# Segment_Register.net
KiCad netlist of a schematic drawn in Altium Designer
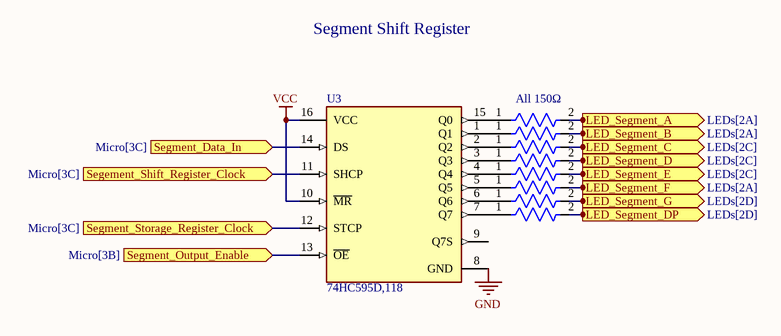
[diagram p0: Segment_Register.SchDoc]

(export (version "E")
  (design (tool "Eeschema 10.0.6"))
  (components
    (comp (ref "R2")
      (value "CRCW0402150RFKED")
      (footprint "FP-CRCW0402-e3-IPC_A")
      (description "RES Thick Film, 150Ω, 1%, 0.063W, 100ppm/°C, 0402")
      (fields (field (name "TOLERANCE") "1%"))
      (libsource (lib "Altium Content Vault") (part "1029c3af85768c4190bb7ad29bc67b5"))
    )
    (comp (ref "R3")
      (value "CRCW0402150RFKED")
      (footprint "FP-CRCW0402-e3-IPC_A")
      (description "RES Thick Film, 150Ω, 1%, 0.063W, 100ppm/°C, 0402")
      (fields (field (name "TOLERANCE") "1%"))
      (libsource (lib "Altium Content Vault") (part "1029c3af85768c4190bb7ad29bc67b5"))
    )
    (comp (ref "R4")
      (value "CRCW0402150RFKED")
      (footprint "FP-CRCW0402-e3-IPC_A")
      (description "RES Thick Film, 150Ω, 1%, 0.063W, 100ppm/°C, 0402")
      (fields (field (name "TOLERANCE") "1%"))
      (libsource (lib "Altium Content Vault") (part "1029c3af85768c4190bb7ad29bc67b5"))
    )
    (comp (ref "R5")
      (value "CRCW0402150RFKED")
      (footprint "FP-CRCW0402-e3-IPC_A")
      (description "RES Thick Film, 150Ω, 1%, 0.063W, 100ppm/°C, 0402")
      (fields (field (name "TOLERANCE") "1%"))
      (libsource (lib "Altium Content Vault") (part "1029c3af85768c4190bb7ad29bc67b5"))
    )
    (comp (ref "R6")
      (value "CRCW0402150RFKED")
      (footprint "FP-CRCW0402-e3-IPC_A")
      (description "RES Thick Film, 150Ω, 1%, 0.063W, 100ppm/°C, 0402")
      (fields (field (name "TOLERANCE") "1%"))
      (libsource (lib "Altium Content Vault") (part "1029c3af85768c4190bb7ad29bc67b5"))
    )
    (comp (ref "R7")
      (value "CRCW0402150RFKED")
      (footprint "FP-CRCW0402-e3-IPC_A")
      (description "RES Thick Film, 150Ω, 1%, 0.063W, 100ppm/°C, 0402")
      (fields (field (name "TOLERANCE") "1%"))
      (libsource (lib "Altium Content Vault") (part "1029c3af85768c4190bb7ad29bc67b5"))
    )
    (comp (ref "R8")
      (value "CRCW0402150RFKED")
      (footprint "FP-CRCW0402-e3-IPC_A")
      (description "RES Thick Film, 150Ω, 1%, 0.063W, 100ppm/°C, 0402")
      (fields (field (name "TOLERANCE") "1%"))
      (libsource (lib "Altium Content Vault") (part "1029c3af85768c4190bb7ad29bc67b5"))
    )
    (comp (ref "R9")
      (value "CRCW0402150RFKED")
      (footprint "FP-CRCW0402-e3-IPC_A")
      (description "RES Thick Film, 150Ω, 1%, 0.063W, 100ppm/°C, 0402")
      (fields (field (name "TOLERANCE") "1%"))
      (libsource (lib "Altium Content Vault") (part "1029c3af85768c4190bb7ad29bc67b5"))
    )
    (comp (ref "U3")
      (value "74HC595D,118")
      (footprint "FP-SOT109-1-IPC_C")
      (description "IC SHIFT REGISTER 8BIT 16SOIC")
      (libsource (lib "Altium Content Vault") (part "7b153f231cfcc3ac06dee253bd56617"))
    )
  )
  (nets
    (net (code "1") (name "/LED_Segment_A") (class "Default")
      (node (ref "R2") (pin "2") (pinfunction "2_2") (pintype "passive"))
    )
    (net (code "2") (name "/LED_Segment_B") (class "Default")
      (node (ref "R3") (pin "2") (pinfunction "2_2") (pintype "passive"))
    )
    (net (code "3") (name "/LED_Segment_C") (class "Default")
      (node (ref "R4") (pin "2") (pinfunction "2_2") (pintype "passive"))
    )
    (net (code "4") (name "/LED_Segment_D") (class "Default")
      (node (ref "R5") (pin "2") (pinfunction "2_2") (pintype "passive"))
    )
    (net (code "5") (name "/LED_Segment_DP") (class "Default")
      (node (ref "R9") (pin "2") (pinfunction "2_2") (pintype "passive"))
    )
    (net (code "6") (name "/LED_Segment_E") (class "Default")
      (node (ref "R6") (pin "2") (pinfunction "2_2") (pintype "passive"))
    )
    (net (code "7") (name "/LED_Segment_F") (class "Default")
      (node (ref "R7") (pin "2") (pinfunction "2_2") (pintype "passive"))
    )
    (net (code "8") (name "/LED_Segment_G") (class "Default")
      (node (ref "R8") (pin "2") (pinfunction "2_2") (pintype "passive"))
    )
    (net (code "9") (name "/Segement_Shift_Register_Clock") (class "Default")
      (node (ref "U3") (pin "11") (pinfunction "SHCP_11") (pintype "input"))
    )
    (net (code "10") (name "/Segment_Data_In") (class "Default")
      (node (ref "U3") (pin "14") (pinfunction "DS_14") (pintype "input"))
    )
    (net (code "11") (name "/Segment_Output_Enable") (class "Default")
      (node (ref "U3") (pin "13") (pinfunction "~{OE}_13") (pintype "input"))
    )
    (net (code "12") (name "/Segment_Storage_Register_Clock") (class "Default")
      (node (ref "U3") (pin "12") (pinfunction "STCP_12") (pintype "input"))
    )
    (net (code "13") (name "GND") (class "Default")
      (node (ref "U3") (pin "8") (pinfunction "GND_8") (pintype "power_in"))
    )
    (net (code "14") (name "Net-(U3-Q0)") (class "Default")
      (node (ref "R2") (pin "1") (pinfunction "1_1") (pintype "passive"))
      (node (ref "U3") (pin "15") (pinfunction "Q0_15") (pintype "output"))
    )
    (net (code "15") (name "Net-(U3-Q1)") (class "Default")
      (node (ref "R3") (pin "1") (pinfunction "1_1") (pintype "passive"))
      (node (ref "U3") (pin "1") (pinfunction "Q1_1") (pintype "output"))
    )
    (net (code "16") (name "Net-(U3-Q2)") (class "Default")
      (node (ref "R4") (pin "1") (pinfunction "1_1") (pintype "passive"))
      (node (ref "U3") (pin "2") (pinfunction "Q2_2") (pintype "output"))
    )
    (net (code "17") (name "Net-(U3-Q3)") (class "Default")
      (node (ref "R5") (pin "1") (pinfunction "1_1") (pintype "passive"))
      (node (ref "U3") (pin "3") (pinfunction "Q3_3") (pintype "output"))
    )
    (net (code "18") (name "Net-(U3-Q4)") (class "Default")
      (node (ref "R6") (pin "1") (pinfunction "1_1") (pintype "passive"))
      (node (ref "U3") (pin "4") (pinfunction "Q4_4") (pintype "output"))
    )
    (net (code "19") (name "Net-(U3-Q5)") (class "Default")
      (node (ref "R7") (pin "1") (pinfunction "1_1") (pintype "passive"))
      (node (ref "U3") (pin "5") (pinfunction "Q5_5") (pintype "output"))
    )
    (net (code "20") (name "Net-(U3-Q6)") (class "Default")
      (node (ref "R8") (pin "1") (pinfunction "1_1") (pintype "passive"))
      (node (ref "U3") (pin "6") (pinfunction "Q6_6") (pintype "output"))
    )
    (net (code "21") (name "Net-(U3-Q7)") (class "Default")
      (node (ref "R9") (pin "1") (pinfunction "1_1") (pintype "passive"))
      (node (ref "U3") (pin "7") (pinfunction "Q7_7") (pintype "output"))
    )
    (net (code "22") (name "VCC") (class "Default")
      (node (ref "U3") (pin "10") (pinfunction "~{MR}_10") (pintype "input"))
      (node (ref "U3") (pin "16") (pinfunction "VCC_16") (pintype "power_in"))
    )
    (net (code "23") (name "unconnected-(U3-Q7S-Pad9)") (class "Default")
      (node (ref "U3") (pin "9") (pinfunction "Q7S_9") (pintype "output"))
    )
  )
)
